# Z_SOLAR_PANEL.net
KiCad netlist of a schematic drawn in EAGLE
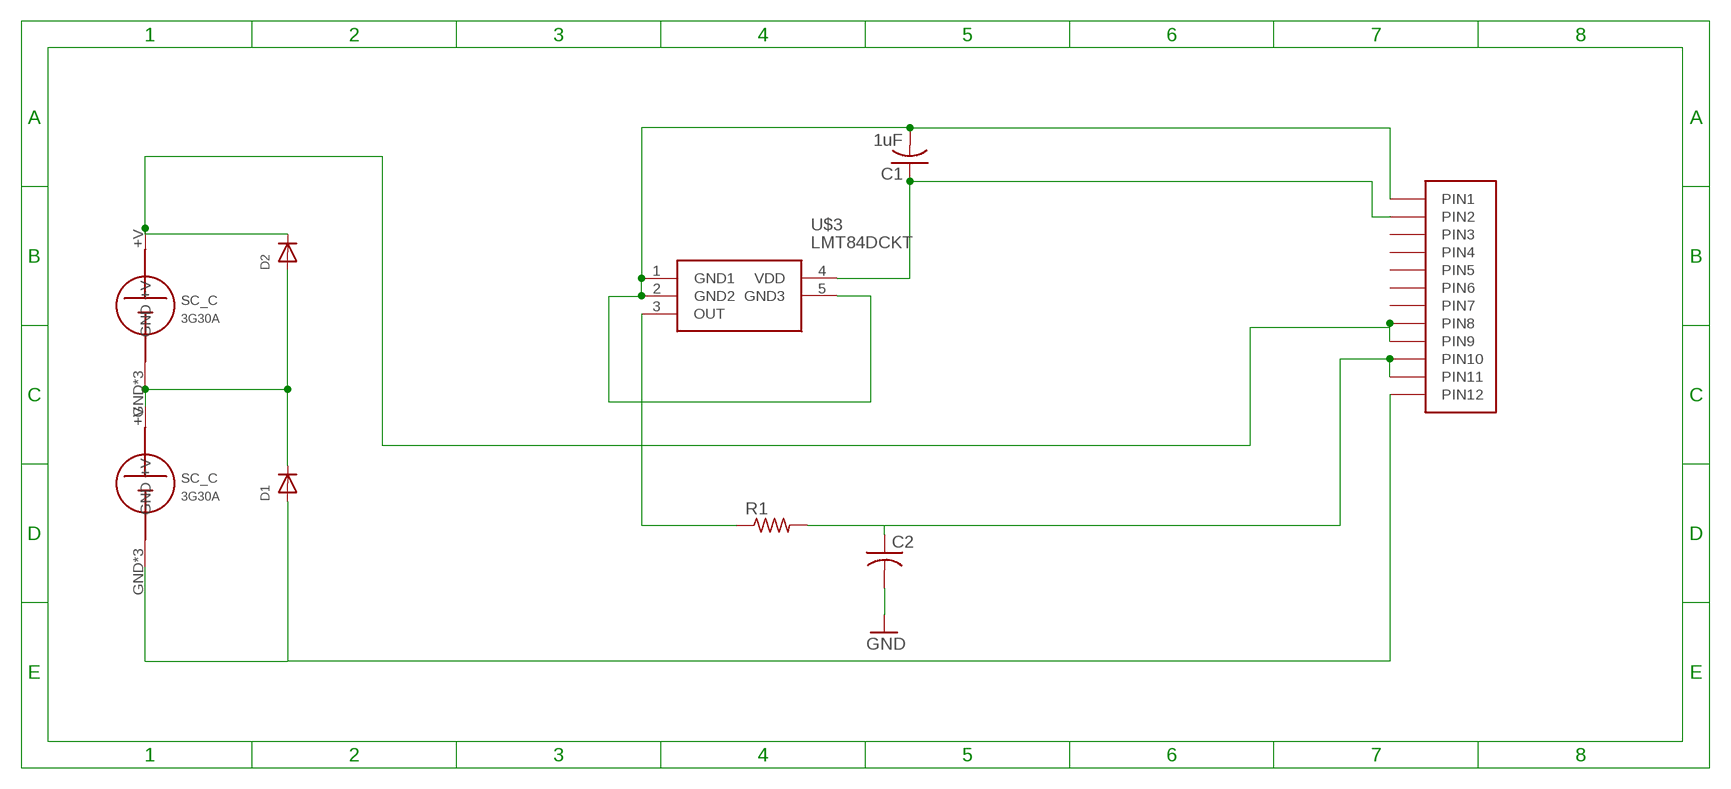
[diagram p0: schematic, sheet 1]

(export (version "E")
  (design (tool "Eeschema 10.0.6"))
  (components
    (comp (ref "C1")
      (value "1uF")
      (footprint "eagle-import:C2012")
      (libsource (lib "eagle-import") (part "C-USC2012"))
    )
    (comp (ref "C2")
      (value "C-USC2012")
      (footprint "eagle-import:C2012")
      (libsource (lib "eagle-import") (part "C-USC2012"))
    )
    (comp (ref "D1")
      (value "DIODE_SOD-123FL")
      (footprint "eagle-import:SOD-123FL")
      (libsource (lib "eagle-import") (part "DIODE_SOD-123FL"))
    )
    (comp (ref "D2")
      (value "DIODE_SOD-123FL")
      (footprint "eagle-import:SOD-123FL")
      (libsource (lib "eagle-import") (part "DIODE_SOD-123FL"))
    )
    (comp (ref "R1")
      (value "R-US_R0402")
      (footprint "eagle-import:R0402")
      (libsource (lib "eagle-import") (part "R-US_R0402"))
    )
    (comp (ref "U$1")
      (value "HEADER12PIN")
      (footprint "eagle-import:HEADER12PIN")
      (libsource (lib "eagle-import") (part "HEADER12PIN"))
    )
    (comp (ref "U$3")
      (value "LMT84DCKT")
      (footprint "eagle-import:SOT65P210X110-5N")
      (fields (field (name "RS_PART_NUMBER") "8115860"))
      (libsource (lib "eagle-import") (part "LMT84DCKT"))
    )
    (comp (ref "U$4")
      (value "SC_C")
      (footprint "eagle-import:SC_C")
      (libsource (lib "eagle-import") (part "SC_C"))
    )
    (comp (ref "U$5")
      (value "SC_C")
      (footprint "eagle-import:SC_C")
      (libsource (lib "eagle-import") (part "SC_C"))
    )
  )
  (nets
    (net (code "1") (name "GND") (class "Default")
      (node (ref "C1") (pin "2") (pinfunction "2_2") (pintype "passive"))
      (node (ref "C2") (pin "2") (pinfunction "2_2") (pintype "passive"))
      (node (ref "D1") (pin "A") (pinfunction "A_A") (pintype "passive"))
      (node (ref "U$1") (pin "P1") (pinfunction "PIN1_P1") (pintype "bidirectional"))
      (node (ref "U$1") (pin "P12") (pinfunction "PIN12_P12") (pintype "bidirectional"))
      (node (ref "U$3") (pin "1") (pinfunction "GND1_1") (pintype "power_in"))
      (node (ref "U$3") (pin "2") (pinfunction "GND2_2") (pintype "power_in"))
      (node (ref "U$3") (pin "5") (pinfunction "GND3_5") (pintype "power_in"))
      (node (ref "U$5") (pin "GND") (pinfunction "GND_GND") (pintype "bidirectional"))
      (node (ref "U$5") (pin "GND1") (pinfunction "GND_GND1") (pintype "bidirectional"))
      (node (ref "U$5") (pin "GND2") (pinfunction "GND_GND2") (pintype "bidirectional"))
    )
    (net (code "2") (name "Net-(D1-PadC)") (class "Default")
      (node (ref "D1") (pin "C") (pinfunction "C_C") (pintype "passive"))
      (node (ref "D2") (pin "A") (pinfunction "A_A") (pintype "passive"))
      (node (ref "U$4") (pin "GND") (pinfunction "GND_GND") (pintype "bidirectional"))
      (node (ref "U$4") (pin "GND1") (pinfunction "GND_GND1") (pintype "bidirectional"))
      (node (ref "U$4") (pin "GND2") (pinfunction "GND_GND2") (pintype "bidirectional"))
      (node (ref "U$5") (pin "+V") (pinfunction "+V_+V") (pintype "bidirectional"))
    )
    (net (code "3") (name "Net-(U$1-PIN2)") (class "Default")
      (node (ref "C1") (pin "1") (pinfunction "1_1") (pintype "passive"))
      (node (ref "U$1") (pin "P2") (pinfunction "PIN2_P2") (pintype "bidirectional"))
      (node (ref "U$3") (pin "4") (pinfunction "VDD_4") (pintype "power_in"))
    )
    (net (code "4") (name "Net-(U$1-PIN8)") (class "Default")
      (node (ref "D2") (pin "C") (pinfunction "C_C") (pintype "passive"))
      (node (ref "U$1") (pin "P8") (pinfunction "PIN8_P8") (pintype "bidirectional"))
      (node (ref "U$1") (pin "P9") (pinfunction "PIN9_P9") (pintype "bidirectional"))
      (node (ref "U$4") (pin "+V") (pinfunction "+V_+V") (pintype "bidirectional"))
    )
    (net (code "5") (name "Net-(U$1-PIN10)") (class "Default")
      (node (ref "C2") (pin "1") (pinfunction "1_1") (pintype "passive"))
      (node (ref "R1") (pin "2") (pinfunction "2_2") (pintype "passive"))
      (node (ref "U$1") (pin "P10") (pinfunction "PIN10_P10") (pintype "bidirectional"))
      (node (ref "U$1") (pin "P11") (pinfunction "PIN11_P11") (pintype "bidirectional"))
    )
    (net (code "6") (name "Net-(U$3-OUT)") (class "Default")
      (node (ref "R1") (pin "1") (pinfunction "1_1") (pintype "passive"))
      (node (ref "U$3") (pin "3") (pinfunction "OUT_3") (pintype "output"))
    )
    (net (code "7") (name "unconnected-(U$1-PIN3-PadP3)") (class "Default")
      (node (ref "U$1") (pin "P3") (pinfunction "PIN3_P3") (pintype "bidirectional"))
    )
    (net (code "8") (name "unconnected-(U$1-PIN4-PadP4)") (class "Default")
      (node (ref "U$1") (pin "P4") (pinfunction "PIN4_P4") (pintype "bidirectional"))
    )
    (net (code "9") (name "unconnected-(U$1-PIN5-PadP5)") (class "Default")
      (node (ref "U$1") (pin "P5") (pinfunction "PIN5_P5") (pintype "bidirectional"))
    )
    (net (code "10") (name "unconnected-(U$1-PIN6-PadP6)") (class "Default")
      (node (ref "U$1") (pin "P6") (pinfunction "PIN6_P6") (pintype "bidirectional"))
    )
    (net (code "11") (name "unconnected-(U$1-PIN7-PadP7)") (class "Default")
      (node (ref "U$1") (pin "P7") (pinfunction "PIN7_P7") (pintype "bidirectional"))
    )
  )
)
